# BattVoltSense.net
KiCad netlist of a schematic drawn in Altium Designer
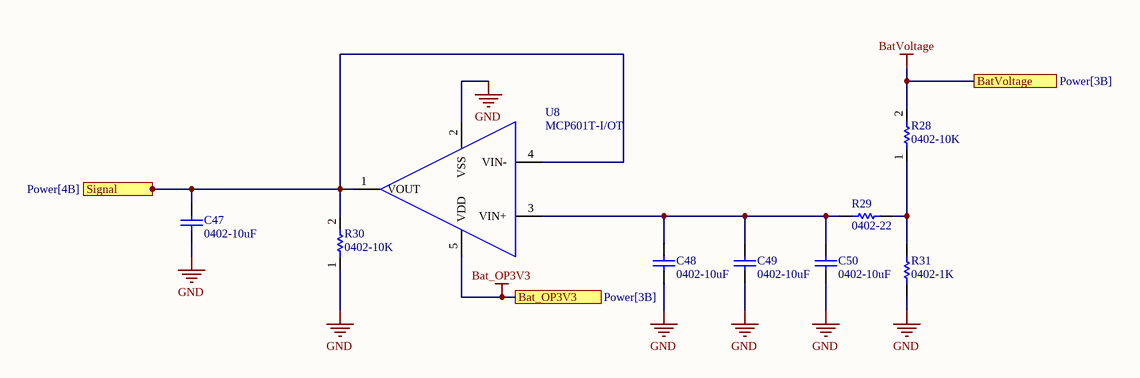
[diagram p0: BattVoltSense.SchDoc]

(export (version "E")
  (design (tool "Eeschema 10.0.6"))
  (components
    (comp (ref "C47")
      (value "0402-10uF")
      (footprint "CAPC0402(1005)60_N")
      (description "Capacitor 10uF 0402s")
      (fields (field (name "TOLERANCE") "20%"))
      (libsource (lib "Tin Tran") (part "0402"))
    )
    (comp (ref "C48")
      (value "0402-10uF")
      (footprint "CAPC0402(1005)60_N")
      (description "Capacitor 10uF 0402s")
      (fields (field (name "TOLERANCE") "20%"))
      (libsource (lib "Tin Tran") (part "0402"))
    )
    (comp (ref "C49")
      (value "0402-10uF")
      (footprint "CAPC0402(1005)60_N")
      (description "Capacitor 10uF 0402s")
      (fields (field (name "TOLERANCE") "20%"))
      (libsource (lib "Tin Tran") (part "0402"))
    )
    (comp (ref "C50")
      (value "0402-10uF")
      (footprint "CAPC0402(1005)60_N")
      (description "Capacitor 10uF 0402s")
      (fields (field (name "TOLERANCE") "20%"))
      (libsource (lib "Tin Tran") (part "0402"))
    )
    (comp (ref "R28")
      (value "0402-10K")
      (footprint "R-0402-10K")
      (description "RES 0402 10K")
      (libsource (lib "") (part "0402_1"))
    )
    (comp (ref "R29")
      (value "0402-22")
      (footprint "R-0402-1K")
      (description "0402Resistor 22Ohm")
      (libsource (lib "") (part "0402_2"))
    )
    (comp (ref "R30")
      (value "0402-10K")
      (footprint "R-0402-10K")
      (description "RES 0402 10K")
      (libsource (lib "") (part "0402_1"))
    )
    (comp (ref "R31")
      (value "0402-1K")
      (footprint "R-0402-1K")
      (description "0402Resistor 1K Ohm")
      (libsource (lib "") (part "0402_2"))
    )
    (comp (ref "U8")
      (value "MCP601T-I/OT")
      (footprint "SOT95P280X145-5N")
      (description "General Purpose Amplifier 1 Circuit Rail-to-Rail SOT-23-5")
      (fields (field (name "MF") "Microchip"))
      (libsource (lib "Tin Tran") (part "MCP601T-I/OT"))
    )
  )
  (nets
    (net (code "1") (name "/Signal") (class "Default")
      (node (ref "C47") (pin "2") (pinfunction "2_2") (pintype "passive"))
      (node (ref "R30") (pin "2") (pinfunction "2_2") (pintype "passive"))
      (node (ref "U8") (pin "1") (pinfunction "VOUT_1") (pintype "passive"))
      (node (ref "U8") (pin "4") (pinfunction "VIN-_4") (pintype "passive"))
    )
    (net (code "2") (name "BatVoltage") (class "Default")
      (node (ref "R28") (pin "2") (pinfunction "2_2") (pintype "passive"))
    )
    (net (code "3") (name "Bat_OP3V3") (class "Default")
      (node (ref "U8") (pin "5") (pinfunction "VDD_5") (pintype "passive"))
    )
    (net (code "4") (name "GND") (class "Default")
      (node (ref "C47") (pin "1") (pinfunction "1_1") (pintype "passive"))
      (node (ref "C48") (pin "1") (pinfunction "1_1") (pintype "passive"))
      (node (ref "C49") (pin "1") (pinfunction "1_1") (pintype "passive"))
      (node (ref "C50") (pin "1") (pinfunction "1_1") (pintype "passive"))
      (node (ref "R30") (pin "1") (pinfunction "1_1") (pintype "passive"))
      (node (ref "R31") (pin "1") (pinfunction "1_1") (pintype "passive"))
      (node (ref "U8") (pin "2") (pinfunction "VSS_2") (pintype "passive"))
    )
    (net (code "5") (name "Net-(R28-Pad1)") (class "Default")
      (node (ref "R28") (pin "1") (pinfunction "1_1") (pintype "passive"))
      (node (ref "R29") (pin "2") (pinfunction "2_2") (pintype "passive"))
      (node (ref "R31") (pin "2") (pinfunction "2_2") (pintype "passive"))
    )
    (net (code "6") (name "Net-(U8-VIN+)") (class "Default")
      (node (ref "C48") (pin "2") (pinfunction "2_2") (pintype "passive"))
      (node (ref "C49") (pin "2") (pinfunction "2_2") (pintype "passive"))
      (node (ref "C50") (pin "2") (pinfunction "2_2") (pintype "passive"))
      (node (ref "R29") (pin "1") (pinfunction "1_1") (pintype "passive"))
      (node (ref "U8") (pin "3") (pinfunction "VIN+_3") (pintype "passive"))
    )
  )
)
